# Baja_Breakout.net
KiCad netlist of a schematic drawn in EAGLE
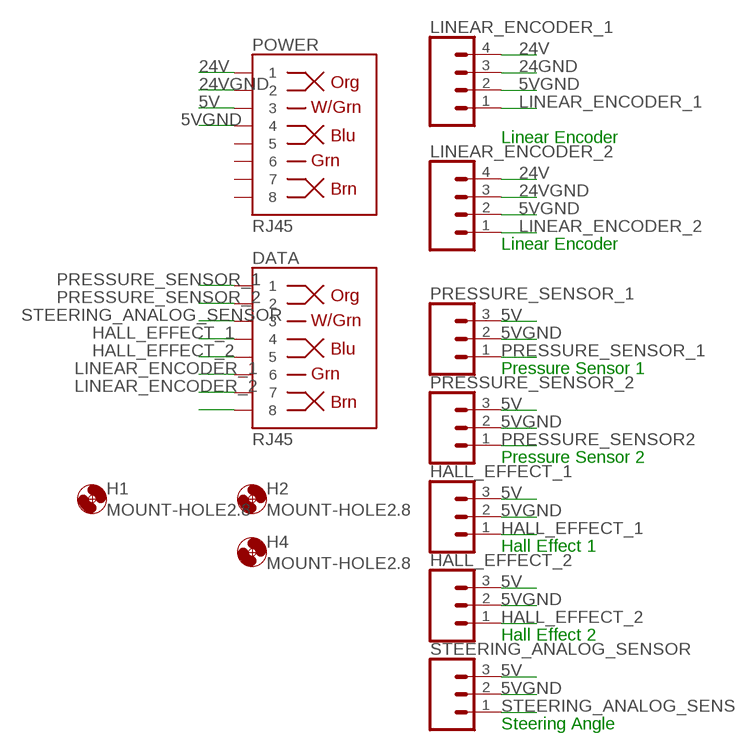
[diagram p0: schematic, sheet 1]

(export (version "E")
  (design (tool "Eeschema 10.0.6"))
  (components
    (comp (ref "DATA")
      (value "RJ45")
      (footprint "eagle-import:RJ45-8")
      (libsource (lib "eagle-import") (part "RJ45-8"))
    )
    (comp (ref "H1")
      (value "MOUNT-HOLE2.8")
      (footprint "eagle-import:2,8")
      (libsource (lib "eagle-import") (part "MOUNT-HOLE2.8"))
    )
    (comp (ref "H2")
      (value "MOUNT-HOLE2.8")
      (footprint "eagle-import:2,8")
      (libsource (lib "eagle-import") (part "MOUNT-HOLE2.8"))
    )
    (comp (ref "H4")
      (value "MOUNT-HOLE2.8")
      (footprint "eagle-import:2,8")
      (libsource (lib "eagle-import") (part "MOUNT-HOLE2.8"))
    )
    (comp (ref "HALL_EFFECT_1")
      (value "CONN_03")
      (footprint "eagle-import:1X03")
      (libsource (lib "eagle-import") (part "CONN_03"))
    )
    (comp (ref "HALL_EFFECT_2")
      (value "CONN_03")
      (footprint "eagle-import:1X03")
      (libsource (lib "eagle-import") (part "CONN_03"))
    )
    (comp (ref "LINEAR_ENCODER_1")
      (value "CONN_04")
      (footprint "eagle-import:1X04")
      (libsource (lib "eagle-import") (part "CONN_04"))
    )
    (comp (ref "LINEAR_ENCODER_2")
      (value "CONN_04")
      (footprint "eagle-import:1X04")
      (libsource (lib "eagle-import") (part "CONN_04"))
    )
    (comp (ref "POWER")
      (value "RJ45")
      (footprint "eagle-import:RJ45-8")
      (libsource (lib "eagle-import") (part "RJ45-8"))
    )
    (comp (ref "PRESSURE_SENSOR_1")
      (value "CONN_03")
      (footprint "eagle-import:1X03")
      (libsource (lib "eagle-import") (part "CONN_03"))
    )
    (comp (ref "PRESSURE_SENSOR_2")
      (value "CONN_03")
      (footprint "eagle-import:1X03")
      (libsource (lib "eagle-import") (part "CONN_03"))
    )
    (comp (ref "STEERING_ANALOG_SENSOR")
      (value "CONN_03")
      (footprint "eagle-import:1X03")
      (libsource (lib "eagle-import") (part "CONN_03"))
    )
  )
  (nets
    (net (code "1") (name "/5V") (class "Default")
      (node (ref "HALL_EFFECT_1") (pin "3") (pinfunction "3_3") (pintype "passive"))
      (node (ref "HALL_EFFECT_2") (pin "3") (pinfunction "3_3") (pintype "passive"))
      (node (ref "POWER") (pin "3") (pinfunction "3_3") (pintype "bidirectional"))
      (node (ref "PRESSURE_SENSOR_1") (pin "3") (pinfunction "3_3") (pintype "passive"))
      (node (ref "PRESSURE_SENSOR_2") (pin "3") (pinfunction "3_3") (pintype "passive"))
      (node (ref "STEERING_ANALOG_SENSOR") (pin "3") (pinfunction "3_3") (pintype "passive"))
    )
    (net (code "2") (name "/5VGND") (class "Default")
      (node (ref "HALL_EFFECT_1") (pin "2") (pinfunction "2_2") (pintype "passive"))
      (node (ref "HALL_EFFECT_2") (pin "2") (pinfunction "2_2") (pintype "passive"))
      (node (ref "LINEAR_ENCODER_1") (pin "2") (pinfunction "2_2") (pintype "passive"))
      (node (ref "LINEAR_ENCODER_2") (pin "2") (pinfunction "2_2") (pintype "passive"))
      (node (ref "POWER") (pin "4") (pinfunction "4_4") (pintype "bidirectional"))
      (node (ref "PRESSURE_SENSOR_1") (pin "2") (pinfunction "2_2") (pintype "passive"))
      (node (ref "PRESSURE_SENSOR_2") (pin "2") (pinfunction "2_2") (pintype "passive"))
      (node (ref "STEERING_ANALOG_SENSOR") (pin "2") (pinfunction "2_2") (pintype "passive"))
    )
    (net (code "3") (name "/24GND") (class "Default")
      (node (ref "LINEAR_ENCODER_1") (pin "3") (pinfunction "3_3") (pintype "passive"))
    )
    (net (code "4") (name "/24V") (class "Default")
      (node (ref "LINEAR_ENCODER_1") (pin "4") (pinfunction "4_4") (pintype "passive"))
      (node (ref "LINEAR_ENCODER_2") (pin "4") (pinfunction "4_4") (pintype "passive"))
      (node (ref "POWER") (pin "1") (pinfunction "1_1") (pintype "bidirectional"))
    )
    (net (code "5") (name "/24VGND") (class "Default")
      (node (ref "LINEAR_ENCODER_2") (pin "3") (pinfunction "3_3") (pintype "passive"))
      (node (ref "POWER") (pin "2") (pinfunction "2_2") (pintype "bidirectional"))
    )
    (net (code "6") (name "/HALL_EFFECT_1") (class "Default")
      (node (ref "DATA") (pin "4") (pinfunction "4_4") (pintype "bidirectional"))
      (node (ref "HALL_EFFECT_1") (pin "1") (pinfunction "1_1") (pintype "passive"))
    )
    (net (code "7") (name "/HALL_EFFECT_2") (class "Default")
      (node (ref "DATA") (pin "5") (pinfunction "5_5") (pintype "bidirectional"))
      (node (ref "HALL_EFFECT_2") (pin "1") (pinfunction "1_1") (pintype "passive"))
    )
    (net (code "8") (name "/LINEAR_ENCODER_1") (class "Default")
      (node (ref "DATA") (pin "6") (pinfunction "6_6") (pintype "bidirectional"))
      (node (ref "LINEAR_ENCODER_1") (pin "1") (pinfunction "1_1") (pintype "passive"))
    )
    (net (code "9") (name "/LINEAR_ENCODER_2") (class "Default")
      (node (ref "DATA") (pin "7") (pinfunction "7_7") (pintype "bidirectional"))
      (node (ref "LINEAR_ENCODER_2") (pin "1") (pinfunction "1_1") (pintype "passive"))
    )
    (net (code "10") (name "/PRESSURE_SENSOR2") (class "Default")
      (node (ref "PRESSURE_SENSOR_2") (pin "1") (pinfunction "1_1") (pintype "passive"))
    )
    (net (code "11") (name "/PRESSURE_SENSOR_1") (class "Default")
      (node (ref "DATA") (pin "1") (pinfunction "1_1") (pintype "bidirectional"))
      (node (ref "PRESSURE_SENSOR_1") (pin "1") (pinfunction "1_1") (pintype "passive"))
    )
    (net (code "12") (name "/PRESSURE_SENSOR_2") (class "Default")
      (node (ref "DATA") (pin "2") (pinfunction "2_2") (pintype "bidirectional"))
    )
    (net (code "13") (name "/STEERING_ANALOG_SENSOR") (class "Default")
      (node (ref "DATA") (pin "3") (pinfunction "3_3") (pintype "bidirectional"))
      (node (ref "STEERING_ANALOG_SENSOR") (pin "1") (pinfunction "1_1") (pintype "passive"))
    )
    (net (code "14") (name "unconnected-(DATA-Pad8)") (class "Default")
      (node (ref "DATA") (pin "8") (pinfunction "8_8") (pintype "bidirectional"))
    )
    (net (code "15") (name "unconnected-(POWER-Pad5)") (class "Default")
      (node (ref "POWER") (pin "5") (pinfunction "5_5") (pintype "bidirectional"))
    )
    (net (code "16") (name "unconnected-(POWER-Pad6)") (class "Default")
      (node (ref "POWER") (pin "6") (pinfunction "6_6") (pintype "bidirectional"))
    )
    (net (code "17") (name "unconnected-(POWER-Pad7)") (class "Default")
      (node (ref "POWER") (pin "7") (pinfunction "7_7") (pintype "bidirectional"))
    )
    (net (code "18") (name "unconnected-(POWER-Pad8)") (class "Default")
      (node (ref "POWER") (pin "8") (pinfunction "8_8") (pintype "bidirectional"))
    )
  )
)
